# GSM_Control_Signals.net
KiCad netlist of a schematic drawn in Altium Designer
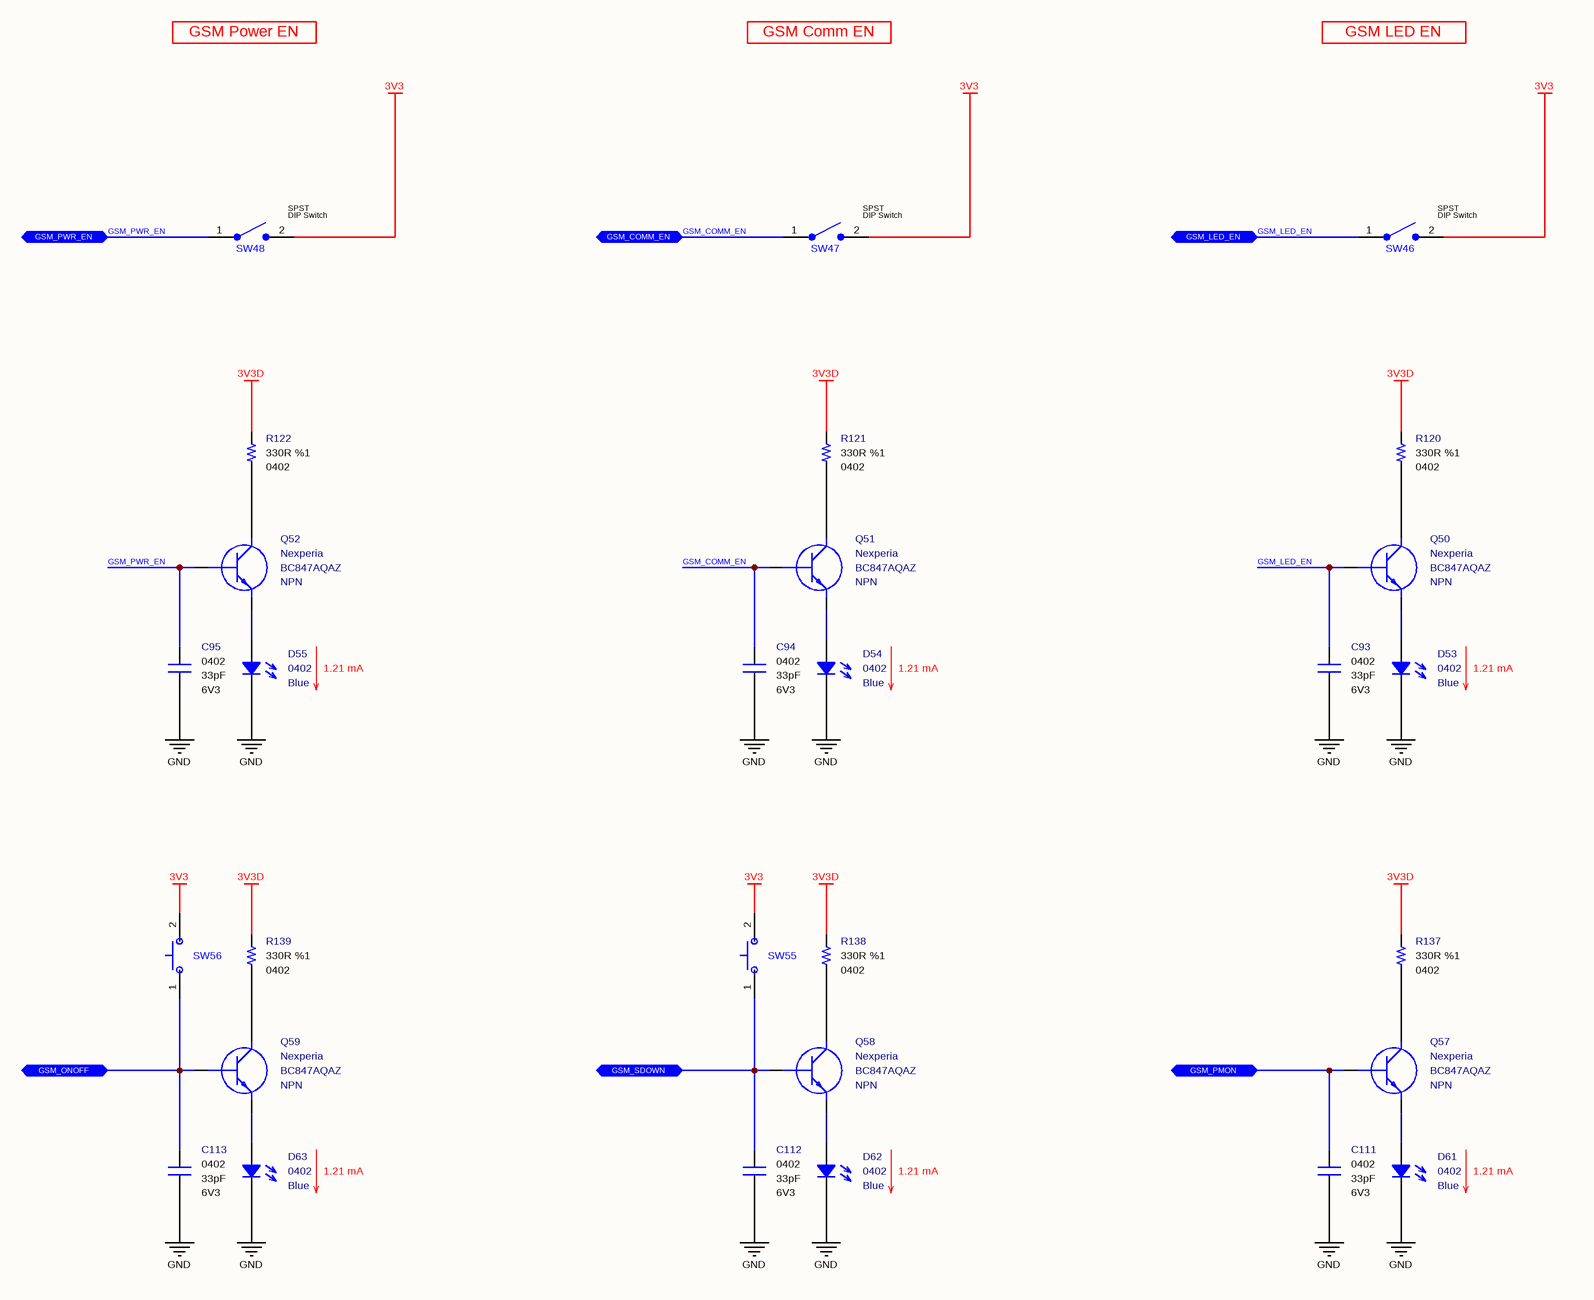
[diagram p0: GSM Control Signals.SchDoc]

(export (version "E")
  (design (tool "Eeschema 10.0.6"))
  (components
    (comp (ref "C93")
      (value "33pF")
      (footprint "CAPACITOR_0402")
      (description "Capacitor - 33pF [0402] (Ceramic)")
      (fields
        (field (name "CASE") "0402")
        (field (name "TOLERANCE") "10%")
        (field (name "VOLTAGE") "6V3")
        (field (name "MANUFACTURER PART NUMBER") "C0402C330J9RACAUTO")
      )
      (libsource (lib "Ovoo_Library") (part "Capacitor - 33pF [0402-6V3]"))
    )
    (comp (ref "C94")
      (value "33pF")
      (footprint "CAPACITOR_0402")
      (description "Capacitor - 33pF [0402] (Ceramic)")
      (fields
        (field (name "CASE") "0402")
        (field (name "TOLERANCE") "10%")
        (field (name "VOLTAGE") "6V3")
        (field (name "MANUFACTURER PART NUMBER") "C0402C330J9RACAUTO")
      )
      (libsource (lib "Ovoo_Library") (part "Capacitor - 33pF [0402-6V3]"))
    )
    (comp (ref "C95")
      (value "33pF")
      (footprint "CAPACITOR_0402")
      (description "Capacitor - 33pF [0402] (Ceramic)")
      (fields
        (field (name "CASE") "0402")
        (field (name "TOLERANCE") "10%")
        (field (name "VOLTAGE") "6V3")
        (field (name "MANUFACTURER PART NUMBER") "C0402C330J9RACAUTO")
      )
      (libsource (lib "Ovoo_Library") (part "Capacitor - 33pF [0402-6V3]"))
    )
    (comp (ref "C111")
      (value "33pF")
      (footprint "CAPACITOR_0402")
      (description "Capacitor - 33pF [0402] (Ceramic)")
      (fields
        (field (name "CASE") "0402")
        (field (name "TOLERANCE") "10%")
        (field (name "VOLTAGE") "6V3")
        (field (name "MANUFACTURER PART NUMBER") "C0402C330J9RACAUTO")
      )
      (libsource (lib "Ovoo_Library") (part "Capacitor - 33pF [0402-6V3]"))
    )
    (comp (ref "C112")
      (value "33pF")
      (footprint "CAPACITOR_0402")
      (description "Capacitor - 33pF [0402] (Ceramic)")
      (fields
        (field (name "CASE") "0402")
        (field (name "TOLERANCE") "10%")
        (field (name "VOLTAGE") "6V3")
        (field (name "MANUFACTURER PART NUMBER") "C0402C330J9RACAUTO")
      )
      (libsource (lib "Ovoo_Library") (part "Capacitor - 33pF [0402-6V3]"))
    )
    (comp (ref "C113")
      (value "33pF")
      (footprint "CAPACITOR_0402")
      (description "Capacitor - 33pF [0402] (Ceramic)")
      (fields
        (field (name "CASE") "0402")
        (field (name "TOLERANCE") "10%")
        (field (name "VOLTAGE") "6V3")
        (field (name "MANUFACTURER PART NUMBER") "C0402C330J9RACAUTO")
      )
      (libsource (lib "Ovoo_Library") (part "Capacitor - 33pF [0402-6V3]"))
    )
    (comp (ref "D53")
      (value "SMD LED (Blue)")
      (footprint "LED_0402")
      (description "Standard LEDs - SMD PICOLEDTM;BLUE LED; 25M @ 5MA")
      (fields
        (field (name "MANUFACTURER_PART_NUMBER") "SMLP13BC8TT86")
        (field (name "MOUSER_PART_NUMBER") "755-SMLP13BC8TT86")
        (field (name "CASE") "0402")
        (field (name "COLOR") "Blue")
      )
      (libsource (lib "Ovoo_Library") (part "Diode - LED (0402-Blue)"))
    )
    (comp (ref "D54")
      (value "SMD LED (Blue)")
      (footprint "LED_0402")
      (description "Standard LEDs - SMD PICOLEDTM;BLUE LED; 25M @ 5MA")
      (fields
        (field (name "MANUFACTURER_PART_NUMBER") "SMLP13BC8TT86")
        (field (name "MOUSER_PART_NUMBER") "755-SMLP13BC8TT86")
        (field (name "CASE") "0402")
        (field (name "COLOR") "Blue")
      )
      (libsource (lib "Ovoo_Library") (part "Diode - LED (0402-Blue)"))
    )
    (comp (ref "D55")
      (value "SMD LED (Blue)")
      (footprint "LED_0402")
      (description "Standard LEDs - SMD PICOLEDTM;BLUE LED; 25M @ 5MA")
      (fields
        (field (name "MANUFACTURER_PART_NUMBER") "SMLP13BC8TT86")
        (field (name "MOUSER_PART_NUMBER") "755-SMLP13BC8TT86")
        (field (name "CASE") "0402")
        (field (name "COLOR") "Blue")
      )
      (libsource (lib "Ovoo_Library") (part "Diode - LED (0402-Blue)"))
    )
    (comp (ref "D61")
      (value "SMD LED (Blue)")
      (footprint "LED_0402")
      (description "Standard LEDs - SMD PICOLEDTM;BLUE LED; 25M @ 5MA")
      (fields
        (field (name "MANUFACTURER_PART_NUMBER") "SMLP13BC8TT86")
        (field (name "MOUSER_PART_NUMBER") "755-SMLP13BC8TT86")
        (field (name "CASE") "0402")
        (field (name "COLOR") "Blue")
      )
      (libsource (lib "Ovoo_Library") (part "Diode - LED (0402-Blue)"))
    )
    (comp (ref "D62")
      (value "SMD LED (Blue)")
      (footprint "LED_0402")
      (description "Standard LEDs - SMD PICOLEDTM;BLUE LED; 25M @ 5MA")
      (fields
        (field (name "MANUFACTURER_PART_NUMBER") "SMLP13BC8TT86")
        (field (name "MOUSER_PART_NUMBER") "755-SMLP13BC8TT86")
        (field (name "CASE") "0402")
        (field (name "COLOR") "Blue")
      )
      (libsource (lib "Ovoo_Library") (part "Diode - LED (0402-Blue)"))
    )
    (comp (ref "D63")
      (value "SMD LED (Blue)")
      (footprint "LED_0402")
      (description "Standard LEDs - SMD PICOLEDTM;BLUE LED; 25M @ 5MA")
      (fields
        (field (name "MANUFACTURER_PART_NUMBER") "SMLP13BC8TT86")
        (field (name "MOUSER_PART_NUMBER") "755-SMLP13BC8TT86")
        (field (name "CASE") "0402")
        (field (name "COLOR") "Blue")
      )
      (libsource (lib "Ovoo_Library") (part "Diode - LED (0402-Blue)"))
    )
    (comp (ref "Q50")
      (value "Bipolar NPN Transistors")
      (footprint "SOT1215")
      (description "Bipolar Transistors - BJT BC847AQA/DFN1010D-3/REEL 7\" Q2")
      (fields
        (field (name "MOUSER_PART_NUMBER") "771-BC847AQAZ")
        (field (name "MANUFACTURER_NAME") "Nexperia")
        (field (name "MANUFACTURER_PART_NUMBER") "BC847AQAZ")
        (field (name "POLARITY") "NPN")
      )
      (libsource (lib "Ovoo_Library") (part "Transistor - BC847"))
    )
    (comp (ref "Q51")
      (value "Bipolar NPN Transistors")
      (footprint "SOT1215")
      (description "Bipolar Transistors - BJT BC847AQA/DFN1010D-3/REEL 7\" Q2")
      (fields
        (field (name "MOUSER_PART_NUMBER") "771-BC847AQAZ")
        (field (name "MANUFACTURER_NAME") "Nexperia")
        (field (name "MANUFACTURER_PART_NUMBER") "BC847AQAZ")
        (field (name "POLARITY") "NPN")
      )
      (libsource (lib "Ovoo_Library") (part "Transistor - BC847"))
    )
    (comp (ref "Q52")
      (value "Bipolar NPN Transistors")
      (footprint "SOT1215")
      (description "Bipolar Transistors - BJT BC847AQA/DFN1010D-3/REEL 7\" Q2")
      (fields
        (field (name "MOUSER_PART_NUMBER") "771-BC847AQAZ")
        (field (name "MANUFACTURER_NAME") "Nexperia")
        (field (name "MANUFACTURER_PART_NUMBER") "BC847AQAZ")
        (field (name "POLARITY") "NPN")
      )
      (libsource (lib "Ovoo_Library") (part "Transistor - BC847"))
    )
    (comp (ref "Q57")
      (value "Bipolar NPN Transistors")
      (footprint "SOT1215")
      (description "Bipolar Transistors - BJT BC847AQA/DFN1010D-3/REEL 7\" Q2")
      (fields
        (field (name "MOUSER_PART_NUMBER") "771-BC847AQAZ")
        (field (name "MANUFACTURER_NAME") "Nexperia")
        (field (name "MANUFACTURER_PART_NUMBER") "BC847AQAZ")
        (field (name "POLARITY") "NPN")
      )
      (libsource (lib "Ovoo_Library") (part "Transistor - BC847"))
    )
    (comp (ref "Q58")
      (value "Bipolar NPN Transistors")
      (footprint "SOT1215")
      (description "Bipolar Transistors - BJT BC847AQA/DFN1010D-3/REEL 7\" Q2")
      (fields
        (field (name "MOUSER_PART_NUMBER") "771-BC847AQAZ")
        (field (name "MANUFACTURER_NAME") "Nexperia")
        (field (name "MANUFACTURER_PART_NUMBER") "BC847AQAZ")
        (field (name "POLARITY") "NPN")
      )
      (libsource (lib "Ovoo_Library") (part "Transistor - BC847"))
    )
    (comp (ref "Q59")
      (value "Bipolar NPN Transistors")
      (footprint "SOT1215")
      (description "Bipolar Transistors - BJT BC847AQA/DFN1010D-3/REEL 7\" Q2")
      (fields
        (field (name "MOUSER_PART_NUMBER") "771-BC847AQAZ")
        (field (name "MANUFACTURER_NAME") "Nexperia")
        (field (name "MANUFACTURER_PART_NUMBER") "BC847AQAZ")
        (field (name "POLARITY") "NPN")
      )
      (libsource (lib "Ovoo_Library") (part "Transistor - BC847"))
    )
    (comp (ref "R120")
      (value "330R")
      (footprint "RESISTOR_0402")
      (description "Thick Film Resistors - SMD 1/16 W 330 Ohm 1%")
      (fields
        (field (name "TOLERANCE") "%1")
        (field (name "CASE") "0402")
        (field (name "MANUFACTURER PART NUMBER") "CRCW0402330RFKED")
        (field (name "MOUSER PART NUMBER") "71-CRCW0402-330-E3")
      )
      (libsource (lib "Ovoo_Library") (part "Resistor - 330R"))
    )
    (comp (ref "R121")
      (value "330R")
      (footprint "RESISTOR_0402")
      (description "Thick Film Resistors - SMD 1/16 W 330 Ohm 1%")
      (fields
        (field (name "TOLERANCE") "%1")
        (field (name "CASE") "0402")
        (field (name "MANUFACTURER PART NUMBER") "CRCW0402330RFKED")
        (field (name "MOUSER PART NUMBER") "71-CRCW0402-330-E3")
      )
      (libsource (lib "Ovoo_Library") (part "Resistor - 330R"))
    )
    (comp (ref "R122")
      (value "330R")
      (footprint "RESISTOR_0402")
      (description "Thick Film Resistors - SMD 1/16 W 330 Ohm 1%")
      (fields
        (field (name "TOLERANCE") "%1")
        (field (name "CASE") "0402")
        (field (name "MANUFACTURER PART NUMBER") "CRCW0402330RFKED")
        (field (name "MOUSER PART NUMBER") "71-CRCW0402-330-E3")
      )
      (libsource (lib "Ovoo_Library") (part "Resistor - 330R"))
    )
    (comp (ref "R137")
      (value "330R")
      (footprint "RESISTOR_0402")
      (description "Thick Film Resistors - SMD 1/16 W 330 Ohm 1%")
      (fields
        (field (name "TOLERANCE") "%1")
        (field (name "CASE") "0402")
        (field (name "MANUFACTURER PART NUMBER") "CRCW0402330RFKED")
        (field (name "MOUSER PART NUMBER") "71-CRCW0402-330-E3")
      )
      (libsource (lib "Ovoo_Library") (part "Resistor - 330R"))
    )
    (comp (ref "R138")
      (value "330R")
      (footprint "RESISTOR_0402")
      (description "Thick Film Resistors - SMD 1/16 W 330 Ohm 1%")
      (fields
        (field (name "TOLERANCE") "%1")
        (field (name "CASE") "0402")
        (field (name "MANUFACTURER PART NUMBER") "CRCW0402330RFKED")
        (field (name "MOUSER PART NUMBER") "71-CRCW0402-330-E3")
      )
      (libsource (lib "Ovoo_Library") (part "Resistor - 330R"))
    )
    (comp (ref "R139")
      (value "330R")
      (footprint "RESISTOR_0402")
      (description "Thick Film Resistors - SMD 1/16 W 330 Ohm 1%")
      (fields
        (field (name "TOLERANCE") "%1")
        (field (name "CASE") "0402")
        (field (name "MANUFACTURER PART NUMBER") "CRCW0402330RFKED")
        (field (name "MOUSER PART NUMBER") "71-CRCW0402-330-E3")
      )
      (libsource (lib "Ovoo_Library") (part "Resistor - 330R"))
    )
    (comp (ref "SW46")
      (value "DIP Switch")
      (footprint "DS04-254-2-01BK-SMT-TR")
      (fields
        (field (name "MANUFACTURER PART NUMBER") "DS04-254-2-01BK-SMT-TR")
        (field (name "MOUSER PART NUMBER") "490-DS04254201BK-STR")
      )
      (libsource (lib "Ovoo_Library") (part "Switch - DIP Switch (1 Pole)"))
    )
    (comp (ref "SW47")
      (value "DIP Switch")
      (footprint "DS04-254-2-01BK-SMT-TR")
      (fields
        (field (name "MANUFACTURER PART NUMBER") "DS04-254-2-01BK-SMT-TR")
        (field (name "MOUSER PART NUMBER") "490-DS04254201BK-STR")
      )
      (libsource (lib "Ovoo_Library") (part "Switch - DIP Switch (1 Pole)"))
    )
    (comp (ref "SW48")
      (value "DIP Switch")
      (footprint "DS04-254-2-01BK-SMT-TR")
      (fields
        (field (name "MANUFACTURER PART NUMBER") "DS04-254-2-01BK-SMT-TR")
        (field (name "MOUSER PART NUMBER") "490-DS04254201BK-STR")
      )
      (libsource (lib "Ovoo_Library") (part "Switch - DIP Switch (1 Pole)"))
    )
    (comp (ref "SW55")
      (value "Tactile Switches")
      (footprint "PTS526_Switch")
      (description "Tactile Switches 50mA 12VDC, 5.2x5.2mm, 0.8mm H, 260gf, G leads.")
      (fields
        (field (name "MANUFACTURER PART NUMBER") "PTS526 SK08 SMTR2 LFS")
        (field (name "MOUSER PART NUMBER") "611-PTS526SK08SMTR2L")
      )
      (libsource (lib "Ovoo_Library") (part "Switch - Tactile"))
    )
    (comp (ref "SW56")
      (value "Tactile Switches")
      (footprint "PTS526_Switch")
      (description "Tactile Switches 50mA 12VDC, 5.2x5.2mm, 0.8mm H, 260gf, G leads.")
      (fields
        (field (name "MANUFACTURER PART NUMBER") "PTS526 SK08 SMTR2 LFS")
        (field (name "MOUSER PART NUMBER") "611-PTS526SK08SMTR2L")
      )
      (libsource (lib "Ovoo_Library") (part "Switch - Tactile"))
    )
  )
  (nets
    (net (code "1") (name "/GSM_COMM_EN") (class "Default")
      (node (ref "C94") (pin "1") (pinfunction "1_1") (pintype "passive"))
      (node (ref "Q51") (pin "1") (pinfunction "B_1") (pintype "passive"))
      (node (ref "SW47") (pin "1") (pinfunction "COM_1") (pintype "passive"))
    )
    (net (code "2") (name "/GSM_LED_EN") (class "Default")
      (node (ref "C93") (pin "1") (pinfunction "1_1") (pintype "passive"))
      (node (ref "Q50") (pin "1") (pinfunction "B_1") (pintype "passive"))
      (node (ref "SW46") (pin "1") (pinfunction "COM_1") (pintype "passive"))
    )
    (net (code "3") (name "/GSM_ONOFF") (class "Default")
      (node (ref "C113") (pin "1") (pinfunction "1_1") (pintype "passive"))
      (node (ref "Q59") (pin "1") (pinfunction "B_1") (pintype "passive"))
      (node (ref "SW56") (pin "1") (pinfunction "NC_1") (pintype "passive"))
    )
    (net (code "4") (name "/GSM_PMON") (class "Default")
      (node (ref "C111") (pin "1") (pinfunction "1_1") (pintype "passive"))
      (node (ref "Q57") (pin "1") (pinfunction "B_1") (pintype "passive"))
    )
    (net (code "5") (name "/GSM_PWR_EN") (class "Default")
      (node (ref "C95") (pin "1") (pinfunction "1_1") (pintype "passive"))
      (node (ref "Q52") (pin "1") (pinfunction "B_1") (pintype "passive"))
      (node (ref "SW48") (pin "1") (pinfunction "COM_1") (pintype "passive"))
    )
    (net (code "6") (name "/GSM_SDOWN") (class "Default")
      (node (ref "C112") (pin "1") (pinfunction "1_1") (pintype "passive"))
      (node (ref "Q58") (pin "1") (pinfunction "B_1") (pintype "passive"))
      (node (ref "SW55") (pin "1") (pinfunction "NC_1") (pintype "passive"))
    )
    (net (code "7") (name "3V3") (class "Default")
      (node (ref "SW46") (pin "2") (pinfunction "NO_2") (pintype "passive"))
      (node (ref "SW47") (pin "2") (pinfunction "NO_2") (pintype "passive"))
      (node (ref "SW48") (pin "2") (pinfunction "NO_2") (pintype "passive"))
      (node (ref "SW55") (pin "2") (pinfunction "COM_2") (pintype "passive"))
      (node (ref "SW56") (pin "2") (pinfunction "COM_2") (pintype "passive"))
    )
    (net (code "8") (name "3V3D") (class "Default")
      (node (ref "R120") (pin "2") (pinfunction "2_2") (pintype "passive"))
      (node (ref "R121") (pin "2") (pinfunction "2_2") (pintype "passive"))
      (node (ref "R122") (pin "2") (pinfunction "2_2") (pintype "passive"))
      (node (ref "R137") (pin "2") (pinfunction "2_2") (pintype "passive"))
      (node (ref "R138") (pin "2") (pinfunction "2_2") (pintype "passive"))
      (node (ref "R139") (pin "2") (pinfunction "2_2") (pintype "passive"))
    )
    (net (code "9") (name "GND") (class "Default")
      (node (ref "C111") (pin "2") (pinfunction "2_2") (pintype "passive"))
      (node (ref "C112") (pin "2") (pinfunction "2_2") (pintype "passive"))
      (node (ref "C113") (pin "2") (pinfunction "2_2") (pintype "passive"))
      (node (ref "C93") (pin "2") (pinfunction "2_2") (pintype "passive"))
      (node (ref "C94") (pin "2") (pinfunction "2_2") (pintype "passive"))
      (node (ref "C95") (pin "2") (pinfunction "2_2") (pintype "passive"))
      (node (ref "D53") (pin "1") (pinfunction "1_1") (pintype "passive"))
      (node (ref "D54") (pin "1") (pinfunction "1_1") (pintype "passive"))
      (node (ref "D55") (pin "1") (pinfunction "1_1") (pintype "passive"))
      (node (ref "D61") (pin "1") (pinfunction "1_1") (pintype "passive"))
      (node (ref "D62") (pin "1") (pinfunction "1_1") (pintype "passive"))
      (node (ref "D63") (pin "1") (pinfunction "1_1") (pintype "passive"))
    )
    (net (code "10") (name "Net-(Q50-C)") (class "Default")
      (node (ref "Q50") (pin "3") (pinfunction "C_3") (pintype "passive"))
      (node (ref "R120") (pin "1") (pinfunction "1_1") (pintype "passive"))
    )
    (net (code "11") (name "Net-(Q50-E)") (class "Default")
      (node (ref "D53") (pin "2") (pinfunction "2_2") (pintype "passive"))
      (node (ref "Q50") (pin "2") (pinfunction "E_2") (pintype "passive"))
    )
    (net (code "12") (name "Net-(Q51-C)") (class "Default")
      (node (ref "Q51") (pin "3") (pinfunction "C_3") (pintype "passive"))
      (node (ref "R121") (pin "1") (pinfunction "1_1") (pintype "passive"))
    )
    (net (code "13") (name "Net-(Q51-E)") (class "Default")
      (node (ref "D54") (pin "2") (pinfunction "2_2") (pintype "passive"))
      (node (ref "Q51") (pin "2") (pinfunction "E_2") (pintype "passive"))
    )
    (net (code "14") (name "Net-(Q52-C)") (class "Default")
      (node (ref "Q52") (pin "3") (pinfunction "C_3") (pintype "passive"))
      (node (ref "R122") (pin "1") (pinfunction "1_1") (pintype "passive"))
    )
    (net (code "15") (name "Net-(Q52-E)") (class "Default")
      (node (ref "D55") (pin "2") (pinfunction "2_2") (pintype "passive"))
      (node (ref "Q52") (pin "2") (pinfunction "E_2") (pintype "passive"))
    )
    (net (code "16") (name "Net-(Q57-C)") (class "Default")
      (node (ref "Q57") (pin "3") (pinfunction "C_3") (pintype "passive"))
      (node (ref "R137") (pin "1") (pinfunction "1_1") (pintype "passive"))
    )
    (net (code "17") (name "Net-(Q57-E)") (class "Default")
      (node (ref "D61") (pin "2") (pinfunction "2_2") (pintype "passive"))
      (node (ref "Q57") (pin "2") (pinfunction "E_2") (pintype "passive"))
    )
    (net (code "18") (name "Net-(Q58-C)") (class "Default")
      (node (ref "Q58") (pin "3") (pinfunction "C_3") (pintype "passive"))
      (node (ref "R138") (pin "1") (pinfunction "1_1") (pintype "passive"))
    )
    (net (code "19") (name "Net-(Q58-E)") (class "Default")
      (node (ref "D62") (pin "2") (pinfunction "2_2") (pintype "passive"))
      (node (ref "Q58") (pin "2") (pinfunction "E_2") (pintype "passive"))
    )
    (net (code "20") (name "Net-(Q59-C)") (class "Default")
      (node (ref "Q59") (pin "3") (pinfunction "C_3") (pintype "passive"))
      (node (ref "R139") (pin "1") (pinfunction "1_1") (pintype "passive"))
    )
    (net (code "21") (name "Net-(Q59-E)") (class "Default")
      (node (ref "D63") (pin "2") (pinfunction "2_2") (pintype "passive"))
      (node (ref "Q59") (pin "2") (pinfunction "E_2") (pintype "passive"))
    )
  )
)
